# controller.net
KiCad netlist of a schematic drawn in EAGLE
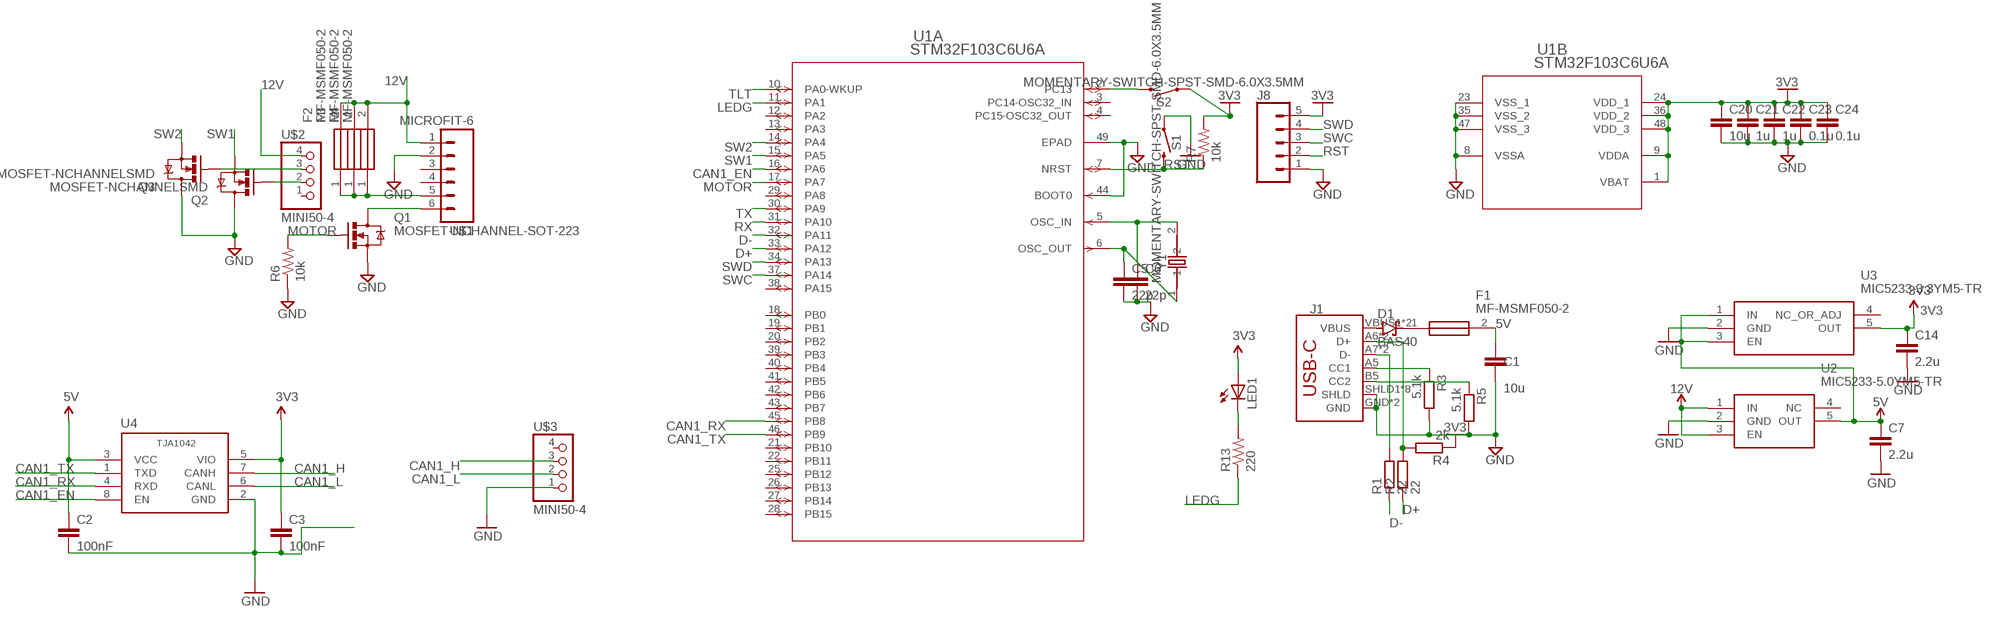
[diagram p0: schematic, sheet 1]

(export (version "E")
  (design (tool "Eeschema 10.0.6"))
  (components
    (comp (ref "C1")
      (value "10u")
      (footprint "eagle-import:0603-C")
      (libsource (lib "eagle-import") (part "C0603"))
    )
    (comp (ref "C2")
      (value "100nF")
      (footprint "eagle-import:0603-C")
      (libsource (lib "eagle-import") (part "C0603"))
    )
    (comp (ref "C3")
      (value "100nF")
      (footprint "eagle-import:0603-C")
      (libsource (lib "eagle-import") (part "C0603"))
    )
    (comp (ref "C5")
      (value "22p")
      (footprint "eagle-import:C1206")
      (libsource (lib "eagle-import") (part "resistor_348_C-EUC1206"))
    )
    (comp (ref "C6")
      (value "22p")
      (footprint "eagle-import:C1206")
      (libsource (lib "eagle-import") (part "resistor_348_C-EUC1206"))
    )
    (comp (ref "C7")
      (value "2.2u")
      (footprint "eagle-import:C0603")
      (libsource (lib "eagle-import") (part "C-EUC0603"))
    )
    (comp (ref "C14")
      (value "2.2u")
      (footprint "eagle-import:C0603")
      (libsource (lib "eagle-import") (part "C-EUC0603"))
    )
    (comp (ref "C20")
      (value "10u")
      (footprint "eagle-import:C1206")
      (libsource (lib "eagle-import") (part "resistor_348_C-EUC1206"))
    )
    (comp (ref "C21")
      (value "1u")
      (footprint "eagle-import:C1206")
      (libsource (lib "eagle-import") (part "resistor_348_C-EUC1206"))
    )
    (comp (ref "C22")
      (value "1u")
      (footprint "eagle-import:C1206")
      (libsource (lib "eagle-import") (part "resistor_348_C-EUC1206"))
    )
    (comp (ref "C23")
      (value "0.1u")
      (footprint "eagle-import:C1206")
      (libsource (lib "eagle-import") (part "resistor_348_C-EUC1206"))
    )
    (comp (ref "C24")
      (value "0.1u")
      (footprint "eagle-import:C1206")
      (libsource (lib "eagle-import") (part "resistor_348_C-EUC1206"))
    )
    (comp (ref "D1")
      (value "BAS40")
      (footprint "eagle-import:SOT23")
      (libsource (lib "eagle-import") (part "BAS40"))
    )
    (comp (ref "F1")
      (value "MF-MSMF050-2")
      (footprint "eagle-import:FUSC4632X85N")
      (fields (field (name "RS_PART_NUMBER") "6478156P"))
      (libsource (lib "eagle-import") (part "MF-MSMF050-2"))
    )
    (comp (ref "F2")
      (value "MF-MSMF050-2")
      (footprint "eagle-import:FUSC4632X85N")
      (fields (field (name "RS_PART_NUMBER") "6478156P"))
      (libsource (lib "eagle-import") (part "MF-MSMF050-2"))
    )
    (comp (ref "F3")
      (value "MF-MSMF050-2")
      (footprint "eagle-import:FUSC4632X85N")
      (fields (field (name "RS_PART_NUMBER") "6478156P"))
      (libsource (lib "eagle-import") (part "MF-MSMF050-2"))
    )
    (comp (ref "F4")
      (value "MF-MSMF050-2")
      (footprint "eagle-import:FUSC4632X85N")
      (fields (field (name "RS_PART_NUMBER") "6478156P"))
      (libsource (lib "eagle-import") (part "MF-MSMF050-2"))
    )
    (comp (ref "J1")
      (value "SPARKFUN-CONNECTORS_USB_C16PIN")
      (footprint "eagle-import:SPARKFUN-CONNECTORS_USB-C-16P")
      (libsource (lib "eagle-import") (part "SPARKFUN-CONNECTORS_USB_C16PIN"))
    )
    (comp (ref "J8")
      (value "CONN_051.27MM")
      (footprint "eagle-import:1X05_1.27MM")
      (libsource (lib "eagle-import") (part "CONN_051.27MM"))
    )
    (comp (ref "LED1")
      (value "LEDCHIPLED_0805")
      (footprint "eagle-import:CHIPLED_0805")
      (libsource (lib "eagle-import") (part "LEDCHIPLED_0805"))
    )
    (comp (ref "Q1")
      (value "MOSFET-NCHANNEL-SOT-223")
      (footprint "eagle-import:SOT-223")
      (libsource (lib "eagle-import") (part "MOSFET-NCHANNEL-SOT-223"))
    )
    (comp (ref "Q2")
      (value "MOSFET-NCHANNELSMD")
      (footprint "eagle-import:SOT23-3")
      (libsource (lib "eagle-import") (part "MOSFET-NCHANNELSMD"))
    )
    (comp (ref "Q3")
      (value "MOSFET-NCHANNELSMD")
      (footprint "eagle-import:SOT23-3")
      (libsource (lib "eagle-import") (part "MOSFET-NCHANNELSMD"))
    )
    (comp (ref "R1")
      (value "22")
      (footprint "eagle-import:R1206")
      (libsource (lib "eagle-import") (part "R-EU_R1206"))
    )
    (comp (ref "R2")
      (value "22")
      (footprint "eagle-import:R1206")
      (libsource (lib "eagle-import") (part "R-EU_R1206"))
    )
    (comp (ref "R3")
      (value "5.1k")
      (footprint "eagle-import:R1206")
      (libsource (lib "eagle-import") (part "resistor_348_R-EU_R1206"))
    )
    (comp (ref "R4")
      (value "2k")
      (footprint "eagle-import:R1206")
      (libsource (lib "eagle-import") (part "resistor_348_R-EU_R1206"))
    )
    (comp (ref "R5")
      (value "5.1k")
      (footprint "eagle-import:R1206")
      (libsource (lib "eagle-import") (part "resistor_348_R-EU_R1206"))
    )
    (comp (ref "R6")
      (value "10k")
      (footprint "eagle-import:0402-R")
      (libsource (lib "eagle-import") (part "R0402"))
    )
    (comp (ref "R7")
      (value "10k")
      (footprint "eagle-import:0402-R")
      (libsource (lib "eagle-import") (part "R0402"))
    )
    (comp (ref "R13")
      (value "220")
      (footprint "eagle-import:0402-R")
      (libsource (lib "eagle-import") (part "R0402"))
    )
    (comp (ref "S1")
      (value "MOMENTARY-SWITCH-SPST-SMD-6.0X3.5MM")
      (footprint "eagle-import:TACTILE_SWITCH_SMD_6.0X3.5MM")
      (libsource (lib "eagle-import") (part "MOMENTARY-SWITCH-SPST-SMD-6.0X3.5MM"))
    )
    (comp (ref "S2")
      (value "MOMENTARY-SWITCH-SPST-SMD-6.0X3.5MM")
      (footprint "eagle-import:TACTILE_SWITCH_SMD_6.0X3.5MM")
      (libsource (lib "eagle-import") (part "MOMENTARY-SWITCH-SPST-SMD-6.0X3.5MM"))
    )
    (comp (ref "U$1")
      (value "MICROFIT-6")
      (footprint "eagle-import:MICROFIT-6")
      (libsource (lib "eagle-import") (part "MICROFIT-6"))
    )
    (comp (ref "U$2")
      (value "MINI50-4")
      (footprint "eagle-import:MINI50")
      (libsource (lib "eagle-import") (part "MINI50-4"))
    )
    (comp (ref "U$3")
      (value "MINI50-4")
      (footprint "eagle-import:MINI50")
      (libsource (lib "eagle-import") (part "MINI50-4"))
    )
    (comp (ref "U1")
      (value "STM32F103C6U6A")
      (footprint "eagle-import:UFQFPN-48_7X7X0P55MM")
      (fields (field (name "COPYRIGHT") "Copyright (C) 2018 Accelerated Designs. All rights reserved"))
      (libsource (lib "eagle-import") (part "STM32F103C6U6A"))
    )
    (comp (ref "U2")
      (value "MIC5233-5.0YM5-TR")
      (footprint "eagle-import:SOT95P280X145-5N")
      (fields (field (name "MOUSER_PART_NUMBER") "998-MIC5233-5.0YM5TR"))
      (libsource (lib "eagle-import") (part "MIC5233-5.0YM5-TR"))
    )
    (comp (ref "U3")
      (value "MIC5233-3.3YM5-TR")
      (footprint "eagle-import:SOT95P280X145-5N")
      (fields (field (name "MOUSER_PART_NUMBER") "998-MIC5233-3.3YM5TR"))
      (libsource (lib "eagle-import") (part "MIC5233-3.3YM5-TR"))
    )
    (comp (ref "U4")
      (value "TJA1042")
      (footprint "eagle-import:NXP_SEMICONDUCTORS_TJA1042T-3-CM_118_0")
      (libsource (lib "eagle-import") (part "TJA1042"))
    )
    (comp (ref "Y1")
      (value "8MHz")
      (footprint "eagle-import:OSCCC500X320X135")
      (fields (field (name "MF") "Shenzen jingpenyuan Co. LTD") (field (name "MP") "5032/2P"))
      (libsource (lib "eagle-import") (part "5032/2P"))
    )
  )
  (nets
    (net (code "1") (name "/CAN1_EN") (class "Default")
      (node (ref "U1") (pin "16") (pinfunction "PA6_16") (pintype "bidirectional"))
      (node (ref "U4") (pin "8") (pinfunction "EN_8") (pintype "bidirectional"))
    )
    (net (code "2") (name "/CAN1_H") (class "Default")
      (node (ref "U$3") (pin "3") (pinfunction "2_3") (pintype "passive"))
      (node (ref "U4") (pin "7") (pinfunction "CANH_7") (pintype "bidirectional"))
    )
    (net (code "3") (name "/CAN1_L") (class "Default")
      (node (ref "U$3") (pin "2") (pinfunction "3_2") (pintype "passive"))
      (node (ref "U4") (pin "6") (pinfunction "CANL_6") (pintype "bidirectional"))
    )
    (net (code "4") (name "/CAN1_RX") (class "Default")
      (node (ref "U1") (pin "45") (pinfunction "PB8_45") (pintype "bidirectional"))
      (node (ref "U4") (pin "4") (pinfunction "RXD_4") (pintype "bidirectional"))
    )
    (net (code "5") (name "/CAN1_TX") (class "Default")
      (node (ref "U1") (pin "46") (pinfunction "PB9_46") (pintype "bidirectional"))
      (node (ref "U4") (pin "1") (pinfunction "TXD_1") (pintype "bidirectional"))
    )
    (net (code "6") (name "/D+") (class "Default")
      (node (ref "R2") (pin "1") (pinfunction "1_1") (pintype "passive"))
      (node (ref "U1") (pin "33") (pinfunction "PA12_33") (pintype "bidirectional"))
    )
    (net (code "7") (name "/D-") (class "Default")
      (node (ref "R1") (pin "1") (pinfunction "1_1") (pintype "passive"))
      (node (ref "U1") (pin "32") (pinfunction "PA11_32") (pintype "bidirectional"))
    )
    (net (code "8") (name "/LEDG") (class "Default")
      (node (ref "R13") (pin "1") (pinfunction "1_1") (pintype "passive"))
      (node (ref "U1") (pin "11") (pinfunction "PA1_11") (pintype "bidirectional"))
    )
    (net (code "9") (name "/MOTOR") (class "Default")
      (node (ref "Q1") (pin "1") (pinfunction "G_1") (pintype "passive"))
      (node (ref "R6") (pin "2") (pinfunction "2_2") (pintype "passive"))
      (node (ref "U1") (pin "17") (pinfunction "PA7_17") (pintype "bidirectional"))
    )
    (net (code "10") (name "/RST") (class "Default")
      (node (ref "J8") (pin "2") (pinfunction "2_2") (pintype "passive"))
      (node (ref "R7") (pin "1") (pinfunction "1_1") (pintype "passive"))
      (node (ref "S1") (pin "2") (pinfunction "2_2") (pintype "passive"))
      (node (ref "U1") (pin "7") (pinfunction "NRST_7") (pintype "bidirectional"))
    )
    (net (code "11") (name "/RX") (class "Default")
      (node (ref "U1") (pin "31") (pinfunction "PA10_31") (pintype "bidirectional"))
    )
    (net (code "12") (name "/SW1") (class "Default")
      (node (ref "Q2") (pin "2") (pinfunction "S_2") (pintype "passive"))
      (node (ref "U1") (pin "15") (pinfunction "PA5_15") (pintype "bidirectional"))
    )
    (net (code "13") (name "/SW2") (class "Default")
      (node (ref "Q3") (pin "2") (pinfunction "S_2") (pintype "passive"))
      (node (ref "U1") (pin "14") (pinfunction "PA4_14") (pintype "bidirectional"))
    )
    (net (code "14") (name "/SWC") (class "Default")
      (node (ref "J8") (pin "3") (pinfunction "3_3") (pintype "passive"))
      (node (ref "U1") (pin "37") (pinfunction "PA14_37") (pintype "bidirectional"))
    )
    (net (code "15") (name "/SWD") (class "Default")
      (node (ref "J8") (pin "4") (pinfunction "4_4") (pintype "passive"))
      (node (ref "U1") (pin "34") (pinfunction "PA13_34") (pintype "bidirectional"))
    )
    (net (code "16") (name "/TLT") (class "Default")
      (node (ref "U1") (pin "10") (pinfunction "PA0-WKUP_10") (pintype "bidirectional"))
    )
    (net (code "17") (name "/TX") (class "Default")
      (node (ref "U1") (pin "30") (pinfunction "PA9_30") (pintype "bidirectional"))
    )
    (net (code "18") (name "3V3") (class "Default")
      (node (ref "C14") (pin "1") (pinfunction "1_1") (pintype "passive"))
      (node (ref "C20") (pin "1") (pinfunction "1_1") (pintype "passive"))
      (node (ref "C21") (pin "1") (pinfunction "1_1") (pintype "passive"))
      (node (ref "C22") (pin "1") (pinfunction "1_1") (pintype "passive"))
      (node (ref "C23") (pin "1") (pinfunction "1_1") (pintype "passive"))
      (node (ref "C24") (pin "1") (pinfunction "1_1") (pintype "passive"))
      (node (ref "C3") (pin "1") (pinfunction "1_1") (pintype "passive"))
      (node (ref "J8") (pin "5") (pinfunction "5_5") (pintype "passive"))
      (node (ref "LED1") (pin "A") (pinfunction "A_A") (pintype "passive"))
      (node (ref "R4") (pin "1") (pinfunction "1_1") (pintype "passive"))
      (node (ref "R7") (pin "2") (pinfunction "2_2") (pintype "passive"))
      (node (ref "S2") (pin "1") (pinfunction "1_1") (pintype "passive"))
      (node (ref "U1") (pin "1") (pinfunction "VBAT_1") (pintype "power_in"))
      (node (ref "U1") (pin "24") (pinfunction "VDD_1_24") (pintype "power_in"))
      (node (ref "U1") (pin "36") (pinfunction "VDD_2_36") (pintype "power_in"))
      (node (ref "U1") (pin "48") (pinfunction "VDD_3_48") (pintype "power_in"))
      (node (ref "U1") (pin "9") (pinfunction "VDDA_9") (pintype "power_in"))
      (node (ref "U3") (pin "5") (pinfunction "OUT_5") (pintype "bidirectional"))
      (node (ref "U4") (pin "5") (pinfunction "VIO_5") (pintype "bidirectional"))
    )
    (net (code "19") (name "5V") (class "Default")
      (node (ref "C1") (pin "1") (pinfunction "1_1") (pintype "passive"))
      (node (ref "C2") (pin "1") (pinfunction "1_1") (pintype "passive"))
      (node (ref "C7") (pin "1") (pinfunction "1_1") (pintype "passive"))
      (node (ref "F1") (pin "2") (pinfunction "2_2") (pintype "bidirectional"))
      (node (ref "U2") (pin "5") (pinfunction "OUT_5") (pintype "bidirectional"))
      (node (ref "U3") (pin "1") (pinfunction "IN_1") (pintype "bidirectional"))
      (node (ref "U3") (pin "3") (pinfunction "EN_3") (pintype "bidirectional"))
      (node (ref "U4") (pin "3") (pinfunction "VCC_3") (pintype "bidirectional"))
    )
    (net (code "20") (name "12V") (class "Default")
      (node (ref "F2") (pin "2") (pinfunction "2_2") (pintype "bidirectional"))
      (node (ref "F3") (pin "2") (pinfunction "2_2") (pintype "bidirectional"))
      (node (ref "F4") (pin "2") (pinfunction "2_2") (pintype "bidirectional"))
      (node (ref "U$1") (pin "1") (pinfunction "1_1") (pintype "passive"))
      (node (ref "U$2") (pin "4") (pinfunction "1_4") (pintype "passive"))
      (node (ref "U2") (pin "1") (pinfunction "IN_1") (pintype "bidirectional"))
      (node (ref "U2") (pin "3") (pinfunction "EN_3") (pintype "bidirectional"))
    )
    (net (code "21") (name "GND") (class "Default")
      (node (ref "C1") (pin "2") (pinfunction "2_2") (pintype "passive"))
      (node (ref "C14") (pin "2") (pinfunction "2_2") (pintype "passive"))
      (node (ref "C2") (pin "2") (pinfunction "2_2") (pintype "passive"))
      (node (ref "C20") (pin "2") (pinfunction "2_2") (pintype "passive"))
      (node (ref "C21") (pin "2") (pinfunction "2_2") (pintype "passive"))
      (node (ref "C22") (pin "2") (pinfunction "2_2") (pintype "passive"))
      (node (ref "C23") (pin "2") (pinfunction "2_2") (pintype "passive"))
      (node (ref "C24") (pin "2") (pinfunction "2_2") (pintype "passive"))
      (node (ref "C3") (pin "2") (pinfunction "2_2") (pintype "passive"))
      (node (ref "C5") (pin "2") (pinfunction "2_2") (pintype "passive"))
      (node (ref "C6") (pin "2") (pinfunction "2_2") (pintype "passive"))
      (node (ref "C7") (pin "2") (pinfunction "2_2") (pintype "passive"))
      (node (ref "J1") (pin "GND") (pinfunction "GND_GND") (pintype "bidirectional"))
      (node (ref "J1") (pin "GND2") (pinfunction "GND_GND2") (pintype "bidirectional"))
      (node (ref "J1") (pin "SHLD1") (pinfunction "SHLD_SHLD1") (pintype "bidirectional"))
      (node (ref "J1") (pin "SHLD2") (pinfunction "SHLD_SHLD2") (pintype "bidirectional"))
      (node (ref "J1") (pin "SHLD3") (pinfunction "SHLD_SHLD3") (pintype "bidirectional"))
      (node (ref "J1") (pin "SHLD4") (pinfunction "SHLD_SHLD4") (pintype "bidirectional"))
      (node (ref "J1") (pin "SHLD5") (pinfunction "SHLD_SHLD5") (pintype "bidirectional"))
      (node (ref "J1") (pin "SHLD6") (pinfunction "SHLD_SHLD6") (pintype "bidirectional"))
      (node (ref "J1") (pin "SHLD7") (pinfunction "SHLD_SHLD7") (pintype "bidirectional"))
      (node (ref "J1") (pin "SHLD8") (pinfunction "SHLD_SHLD8") (pintype "bidirectional"))
      (node (ref "J8") (pin "1") (pinfunction "1_1") (pintype "passive"))
      (node (ref "Q1") (pin "3") (pinfunction "S_3") (pintype "passive"))
      (node (ref "Q2") (pin "3") (pinfunction "D_3") (pintype "passive"))
      (node (ref "Q3") (pin "3") (pinfunction "D_3") (pintype "passive"))
      (node (ref "R3") (pin "2") (pinfunction "2_2") (pintype "passive"))
      (node (ref "R5") (pin "2") (pinfunction "2_2") (pintype "passive"))
      (node (ref "R6") (pin "1") (pinfunction "1_1") (pintype "passive"))
      (node (ref "S1") (pin "1") (pinfunction "1_1") (pintype "passive"))
      (node (ref "U$1") (pin "2") (pinfunction "2_2") (pintype "passive"))
      (node (ref "U$3") (pin "1") (pinfunction "4_1") (pintype "passive"))
      (node (ref "U1") (pin "23") (pinfunction "VSS_1_23") (pintype "power_in"))
      (node (ref "U1") (pin "35") (pinfunction "VSS_2_35") (pintype "power_in"))
      (node (ref "U1") (pin "44") (pinfunction "BOOT0_44") (pintype "input"))
      (node (ref "U1") (pin "47") (pinfunction "VSS_3_47") (pintype "power_in"))
      (node (ref "U1") (pin "49") (pinfunction "EPAD_49") (pintype "passive"))
      (node (ref "U1") (pin "8") (pinfunction "VSSA_8") (pintype "power_in"))
      (node (ref "U2") (pin "2") (pinfunction "GND_2") (pintype "bidirectional"))
      (node (ref "U3") (pin "2") (pinfunction "GND_2") (pintype "bidirectional"))
      (node (ref "U4") (pin "2") (pinfunction "GND_2") (pintype "bidirectional"))
    )
    (net (code "22") (name "Net-(D1-A)") (class "Default")
      (node (ref "D1") (pin "1") (pinfunction "A_1") (pintype "passive"))
      (node (ref "J1") (pin "VBUS1") (pinfunction "VBUS_VBUS1") (pintype "bidirectional"))
      (node (ref "J1") (pin "VBUS2") (pinfunction "VBUS_VBUS2") (pintype "bidirectional"))
    )
    (net (code "23") (name "Net-(D1-C)") (class "Default")
      (node (ref "D1") (pin "3") (pinfunction "C_3") (pintype "passive"))
      (node (ref "F1") (pin "1") (pinfunction "1_1") (pintype "bidirectional"))
    )
    (net (code "24") (name "Net-(F2-Pad1)") (class "Default")
      (node (ref "F2") (pin "1") (pinfunction "1_1") (pintype "bidirectional"))
      (node (ref "F3") (pin "1") (pinfunction "1_1") (pintype "bidirectional"))
      (node (ref "F4") (pin "1") (pinfunction "1_1") (pintype "bidirectional"))
      (node (ref "U$1") (pin "5") (pinfunction "5_5") (pintype "passive"))
    )
    (net (code "25") (name "Net-(J1-CC1)") (class "Default")
      (node (ref "J1") (pin "A5") (pinfunction "CC1_A5") (pintype "bidirectional"))
      (node (ref "R3") (pin "1") (pinfunction "1_1") (pintype "passive"))
    )
    (net (code "26") (name "Net-(J1-CC2)") (class "Default")
      (node (ref "J1") (pin "B5") (pinfunction "CC2_B5") (pintype "bidirectional"))
      (node (ref "R5") (pin "1") (pinfunction "1_1") (pintype "passive"))
    )
    (net (code "27") (name "Net-(J1-D+-PadA6)") (class "Default")
      (node (ref "J1") (pin "A6") (pinfunction "D+_A6") (pintype "bidirectional"))
      (node (ref "J1") (pin "B6") (pinfunction "D+_B6") (pintype "bidirectional"))
      (node (ref "R2") (pin "2") (pinfunction "2_2") (pintype "passive"))
      (node (ref "R4") (pin "2") (pinfunction "2_2") (pintype "passive"))
    )
    (net (code "28") (name "Net-(J1-D--PadA7)") (class "Default")
      (node (ref "J1") (pin "A7") (pinfunction "D-_A7") (pintype "bidirectional"))
      (node (ref "J1") (pin "B7") (pinfunction "D-_B7") (pintype "bidirectional"))
      (node (ref "R1") (pin "2") (pinfunction "2_2") (pintype "passive"))
    )
    (net (code "29") (name "Net-(LED1-PadC)") (class "Default")
      (node (ref "LED1") (pin "C") (pinfunction "C_C") (pintype "passive"))
      (node (ref "R13") (pin "2") (pinfunction "2_2") (pintype "passive"))
    )
    (net (code "30") (name "Net-(Q1-D-Pad2)") (class "Default")
      (node (ref "Q1") (pin "2") (pinfunction "D_2") (pintype "passive"))
      (node (ref "Q1") (pin "4") (pinfunction "D_4") (pintype "passive"))
      (node (ref "U$1") (pin "6") (pinfunction "6_6") (pintype "passive"))
    )
    (net (code "31") (name "Net-(Q2-G)") (class "Default")
      (node (ref "Q2") (pin "1") (pinfunction "G_1") (pintype "passive"))
      (node (ref "U$2") (pin "2") (pinfunction "3_2") (pintype "passive"))
    )
    (net (code "32") (name "Net-(Q3-G)") (class "Default")
      (node (ref "Q3") (pin "1") (pinfunction "G_1") (pintype "passive"))
      (node (ref "U$2") (pin "3") (pinfunction "2_3") (pintype "passive"))
    )
    (net (code "33") (name "Net-(U1A-OSC_IN)") (class "Default")
      (node (ref "C6") (pin "1") (pinfunction "1_1") (pintype "passive"))
      (node (ref "U1") (pin "5") (pinfunction "OSC_IN_5") (pintype "input"))
      (node (ref "Y1") (pin "2") (pinfunction "2_2") (pintype "passive"))
    )
    (net (code "34") (name "Net-(U1A-OSC_OUT)") (class "Default")
      (node (ref "C5") (pin "1") (pinfunction "1_1") (pintype "passive"))
      (node (ref "U1") (pin "6") (pinfunction "OSC_OUT_6") (pintype "output"))
      (node (ref "Y1") (pin "1") (pinfunction "1_1") (pintype "passive"))
    )
    (net (code "35") (name "Net-(U1A-PC13)") (class "Default")
      (node (ref "S2") (pin "2") (pinfunction "2_2") (pintype "passive"))
      (node (ref "U1") (pin "2") (pinfunction "PC13_2") (pintype "bidirectional"))
    )
    (net (code "36") (name "unconnected-(U$1-Pad3)") (class "Default")
      (node (ref "U$1") (pin "3") (pinfunction "3_3") (pintype "passive"))
    )
    (net (code "37") (name "unconnected-(U$1-Pad4)") (class "Default")
      (node (ref "U$1") (pin "4") (pinfunction "4_4") (pintype "passive"))
    )
    (net (code "38") (name "unconnected-(U$2-4-Pad1)") (class "Default")
      (node (ref "U$2") (pin "1") (pinfunction "4_1") (pintype "passive"))
    )
    (net (code "39") (name "unconnected-(U$3-1-Pad4)") (class "Default")
      (node (ref "U$3") (pin "4") (pinfunction "1_4") (pintype "passive"))
    )
    (net (code "40") (name "unconnected-(U1A-PA2-Pad12)") (class "Default")
      (node (ref "U1") (pin "12") (pinfunction "PA2_12") (pintype "bidirectional"))
    )
    (net (code "41") (name "unconnected-(U1A-PA3-Pad13)") (class "Default")
      (node (ref "U1") (pin "13") (pinfunction "PA3_13") (pintype "bidirectional"))
    )
    (net (code "42") (name "unconnected-(U1A-PA8-Pad29)") (class "Default")
      (node (ref "U1") (pin "29") (pinfunction "PA8_29") (pintype "bidirectional"))
    )
    (net (code "43") (name "unconnected-(U1A-PA15-Pad38)") (class "Default")
      (node (ref "U1") (pin "38") (pinfunction "PA15_38") (pintype "bidirectional"))
    )
    (net (code "44") (name "unconnected-(U1A-PB0-Pad18)") (class "Default")
      (node (ref "U1") (pin "18") (pinfunction "PB0_18") (pintype "bidirectional"))
    )
    (net (code "45") (name "unconnected-(U1A-PB1-Pad19)") (class "Default")
      (node (ref "U1") (pin "19") (pinfunction "PB1_19") (pintype "bidirectional"))
    )
    (net (code "46") (name "unconnected-(U1A-PB2-Pad20)") (class "Default")
      (node (ref "U1") (pin "20") (pinfunction "PB2_20") (pintype "bidirectional"))
    )
    (net (code "47") (name "unconnected-(U1A-PB3-Pad39)") (class "Default")
      (node (ref "U1") (pin "39") (pinfunction "PB3_39") (pintype "bidirectional"))
    )
    (net (code "48") (name "unconnected-(U1A-PB4-Pad40)") (class "Default")
      (node (ref "U1") (pin "40") (pinfunction "PB4_40") (pintype "bidirectional"))
    )
    (net (code "49") (name "unconnected-(U1A-PB5-Pad41)") (class "Default")
      (node (ref "U1") (pin "41") (pinfunction "PB5_41") (pintype "bidirectional"))
    )
    (net (code "50") (name "unconnected-(U1A-PB6-Pad42)") (class "Default")
      (node (ref "U1") (pin "42") (pinfunction "PB6_42") (pintype "bidirectional"))
    )
    (net (code "51") (name "unconnected-(U1A-PB7-Pad43)") (class "Default")
      (node (ref "U1") (pin "43") (pinfunction "PB7_43") (pintype "bidirectional"))
    )
    (net (code "52") (name "unconnected-(U1A-PB10-Pad21)") (class "Default")
      (node (ref "U1") (pin "21") (pinfunction "PB10_21") (pintype "bidirectional"))
    )
    (net (code "53") (name "unconnected-(U1A-PB11-Pad22)") (class "Default")
      (node (ref "U1") (pin "22") (pinfunction "PB11_22") (pintype "bidirectional"))
    )
    (net (code "54") (name "unconnected-(U1A-PB12-Pad25)") (class "Default")
      (node (ref "U1") (pin "25") (pinfunction "PB12_25") (pintype "bidirectional"))
    )
    (net (code "55") (name "unconnected-(U1A-PB13-Pad26)") (class "Default")
      (node (ref "U1") (pin "26") (pinfunction "PB13_26") (pintype "bidirectional"))
    )
    (net (code "56") (name "unconnected-(U1A-PB14-Pad27)") (class "Default")
      (node (ref "U1") (pin "27") (pinfunction "PB14_27") (pintype "bidirectional"))
    )
    (net (code "57") (name "unconnected-(U1A-PB15-Pad28)") (class "Default")
      (node (ref "U1") (pin "28") (pinfunction "PB15_28") (pintype "bidirectional"))
    )
    (net (code "58") (name "unconnected-(U1A-PC14-OSC32_IN-Pad3)") (class "Default")
      (node (ref "U1") (pin "3") (pinfunction "PC14-OSC32_IN_3") (pintype "bidirectional"))
    )
    (net (code "59") (name "unconnected-(U1A-PC15-OSC32_OUT-Pad4)") (class "Default")
      (node (ref "U1") (pin "4") (pinfunction "PC15-OSC32_OUT_4") (pintype "bidirectional"))
    )
    (net (code "60") (name "unconnected-(U2-NC-Pad4)") (class "Default")
      (node (ref "U2") (pin "4") (pinfunction "NC_4") (pintype "no_connect"))
    )
    (net (code "61") (name "unconnected-(U3-NC_OR_ADJ-Pad4)") (class "Default")
      (node (ref "U3") (pin "4") (pinfunction "NC_OR_ADJ_4") (pintype "bidirectional"))
    )
  )
)
